# rf_lpf_30_20.net
KiCad netlist of a schematic drawn in Altium Designer
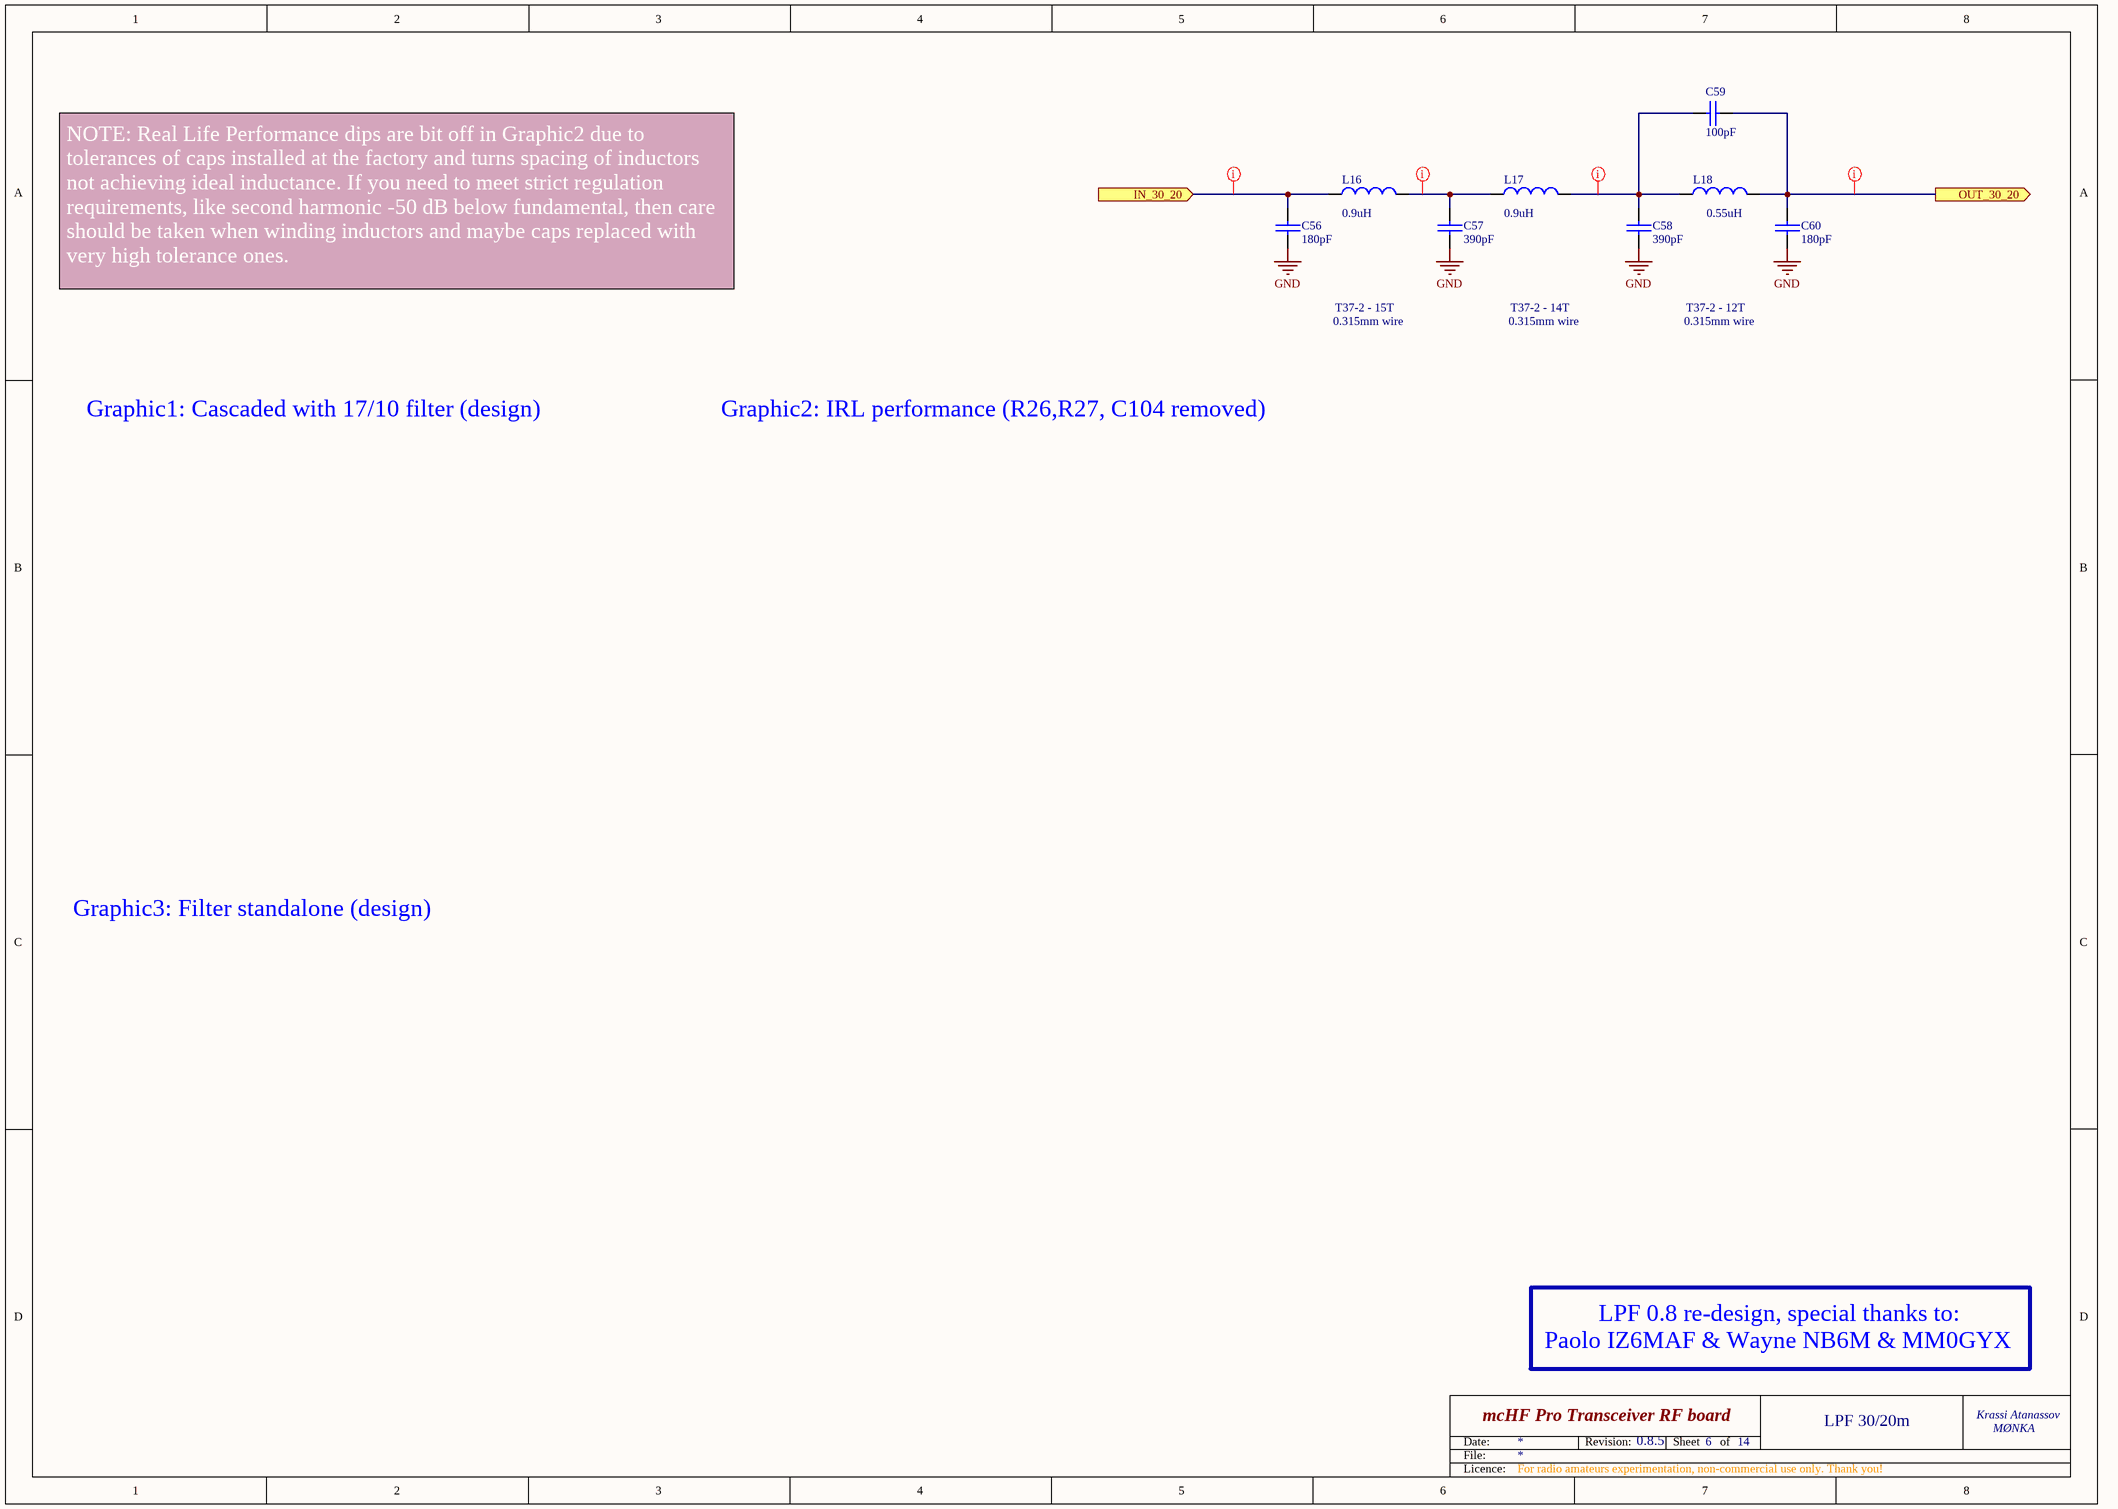
[diagram p0: rf_lpf_30_20.SchDoc]

(export (version "E")
  (design (tool "Eeschema 10.0.6"))
  (components
    (comp (ref "C56")
      (value "180pF")
      (footprint "0805")
      (description "Capacitor")
      (fields (field (name "VOLTAGE") "100V"))
      (libsource (lib "mcHF_rf") (part "CAP"))
    )
    (comp (ref "C57")
      (value "390pF")
      (footprint "0805")
      (description "Capacitor")
      (fields (field (name "VOLTAGE") "100V"))
      (libsource (lib "mcHF_rf") (part "CAP"))
    )
    (comp (ref "C58")
      (value "390pF")
      (footprint "0805")
      (description "Capacitor")
      (fields (field (name "VOLTAGE") "100V"))
      (libsource (lib "mcHF_rf") (part "CAP"))
    )
    (comp (ref "C59")
      (value "100pF")
      (footprint "0805")
      (description "Capacitor")
      (fields (field (name "VOLTAGE") "100V"))
      (libsource (lib "mcHF_rf") (part "CAP"))
    )
    (comp (ref "C60")
      (value "180pF")
      (footprint "0805")
      (description "Capacitor")
      (fields (field (name "VOLTAGE") "100V"))
      (libsource (lib "mcHF_rf") (part "CAP"))
    )
    (comp (ref "L16")
      (value "T37-2")
      (footprint "LPF_IND")
      (description "T37-2 handwound inductor")
      (fields (field (name "INDUCTANCE") "0.9uH"))
      (libsource (lib "mcHF_rf") (part "LPF_IND"))
    )
    (comp (ref "L17")
      (value "T37-2")
      (footprint "LPF_IND")
      (description "T37-2 handwound inductor")
      (fields (field (name "INDUCTANCE") "0.9uH"))
      (libsource (lib "mcHF_rf") (part "LPF_IND"))
    )
    (comp (ref "L18")
      (value "T37-2")
      (footprint "LPF_IND")
      (description "T37-2 handwound inductor")
      (fields (field (name "INDUCTANCE") "0.55uH"))
      (libsource (lib "mcHF_rf") (part "LPF_IND"))
    )
  )
  (nets
    (net (code "1") (name "/IN_30_20") (class "Default")
      (node (ref "C56") (pin "2") (pinfunction "2_2") (pintype "passive"))
      (node (ref "L16") (pin "1") (pinfunction "1_1") (pintype "passive"))
    )
    (net (code "2") (name "/OUT_30_20") (class "Default")
      (node (ref "C59") (pin "1") (pinfunction "1_1") (pintype "passive"))
      (node (ref "C60") (pin "2") (pinfunction "2_2") (pintype "passive"))
      (node (ref "L18") (pin "2") (pinfunction "2_2") (pintype "passive"))
    )
    (net (code "3") (name "GND") (class "Default")
      (node (ref "C56") (pin "1") (pinfunction "1_1") (pintype "passive"))
      (node (ref "C57") (pin "1") (pinfunction "1_1") (pintype "passive"))
      (node (ref "C58") (pin "1") (pinfunction "1_1") (pintype "passive"))
      (node (ref "C60") (pin "1") (pinfunction "1_1") (pintype "passive"))
    )
    (net (code "4") (name "Net-(C57-Pad2)") (class "Default")
      (node (ref "C57") (pin "2") (pinfunction "2_2") (pintype "passive"))
      (node (ref "L16") (pin "2") (pinfunction "2_2") (pintype "passive"))
      (node (ref "L17") (pin "1") (pinfunction "1_1") (pintype "passive"))
    )
    (net (code "5") (name "Net-(C58-Pad2)") (class "Default")
      (node (ref "C58") (pin "2") (pinfunction "2_2") (pintype "passive"))
      (node (ref "C59") (pin "2") (pinfunction "2_2") (pintype "passive"))
      (node (ref "L17") (pin "2") (pinfunction "2_2") (pintype "passive"))
      (node (ref "L18") (pin "1") (pinfunction "1_1") (pintype "passive"))
    )
  )
)
